# CPU.net
KiCad netlist of a schematic drawn in Altium Designer
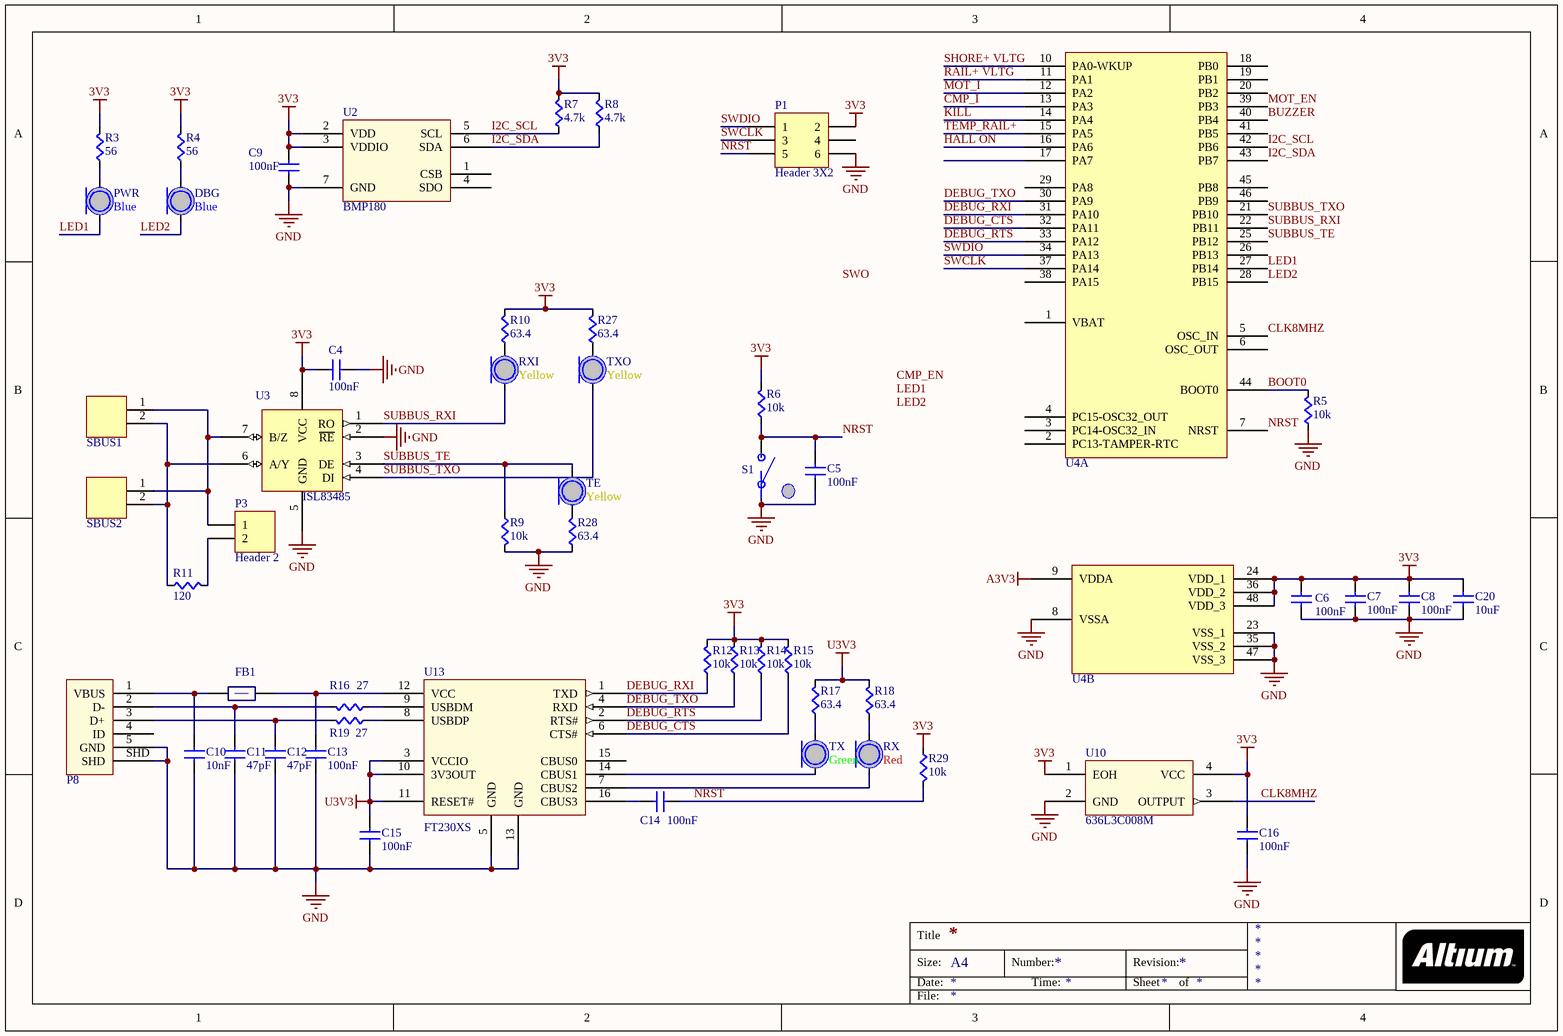
[diagram p0: CPU.SchDoc]

(export (version "E")
  (design (tool "Eeschema 10.0.6"))
  (components
    (comp (ref "C4")
      (value "100nF")
      (footprint "CAPC0603")
      (fields (field (name "Comment") "Cap"))
      (libsource (lib "SubjuGator8") (part "Cap"))
    )
    (comp (ref "C5")
      (value "100nF")
      (footprint "CAPC0603")
      (fields (field (name "Comment") "Cap"))
      (libsource (lib "SubjuGator8") (part "Cap"))
    )
    (comp (ref "C6")
      (value "100nF")
      (footprint "CAPC0603")
      (fields (field (name "Comment") "Cap"))
      (libsource (lib "SubjuGator8") (part "Cap"))
    )
    (comp (ref "C7")
      (value "100nF")
      (footprint "CAPC0603")
      (fields (field (name "Comment") "Cap"))
      (libsource (lib "SubjuGator8") (part "Cap"))
    )
    (comp (ref "C8")
      (value "100nF")
      (footprint "CAPC0603")
      (fields (field (name "Comment") "Cap"))
      (libsource (lib "SubjuGator8") (part "Cap"))
    )
    (comp (ref "C9")
      (value "100nF")
      (footprint "CAPC0603")
      (fields (field (name "Comment") "Cap"))
      (libsource (lib "SubjuGator8") (part "Cap"))
    )
    (comp (ref "C10")
      (value "10nF")
      (footprint "CAPC0603")
      (fields (field (name "Comment") "Cap"))
      (libsource (lib "SubjuGator8") (part "Cap"))
    )
    (comp (ref "C11")
      (value "47pF")
      (footprint "CAPC0603")
      (fields (field (name "Comment") "Cap"))
      (libsource (lib "SubjuGator8") (part "Cap"))
    )
    (comp (ref "C12")
      (value "47pF")
      (footprint "CAPC0603")
      (fields (field (name "Comment") "Cap"))
      (libsource (lib "SubjuGator8") (part "Cap"))
    )
    (comp (ref "C13")
      (value "100nF")
      (footprint "CAPC0603")
      (fields (field (name "Comment") "Cap"))
      (libsource (lib "SubjuGator8") (part "Cap"))
    )
    (comp (ref "C14")
      (value "100nF")
      (footprint "CAPC0603")
      (fields (field (name "Comment") "Cap"))
      (libsource (lib "SubjuGator8") (part "Cap"))
    )
    (comp (ref "C15")
      (value "100nF")
      (footprint "CAPC0603")
      (fields (field (name "Comment") "Cap"))
      (libsource (lib "SubjuGator8") (part "Cap"))
    )
    (comp (ref "C16")
      (value "100nF")
      (footprint "CAPC0603")
      (fields (field (name "Comment") "Cap"))
      (libsource (lib "SubjuGator8") (part "Cap"))
    )
    (comp (ref "C20")
      (value "10uF")
      (footprint "CAPC1206")
      (fields (field (name "Comment") "Cap"))
      (libsource (lib "SubjuGator8") (part "Cap"))
    )
    (comp (ref "DBG")
      (value "LED")
      (footprint "LED0805")
      (fields (field (name "COLOR") "Blue"))
      (libsource (lib "SubjuGator8") (part "LED"))
    )
    (comp (ref "FB1")
      (value "FBead")
      (footprint "RES0603")
      (description "Ferrite Bead")
      (libsource (lib "SubjuGator8") (part "FBead"))
    )
    (comp (ref "P1")
      (value "Header 3X2")
      (footprint "HDR2X3")
      (description "Header, 3-Pin, Dual row")
      (fields (field (name "PUBLISHER") "Altium Limited"))
      (libsource (lib "Miscellaneous Connectors") (part "Header 3X2"))
    )
    (comp (ref "P3")
      (value "Header 2")
      (footprint "HDR1X2")
      (description "Header, 2-Pin")
      (fields (field (name "PUBLISHER") "Altium Limited"))
      (libsource (lib "Miscellaneous Connectors") (part "Header 2"))
    )
    (comp (ref "P8")
      (value "UX60SC-MB-5ST")
      (footprint "UX60SC-MB-5ST")
      (description "USB Mini B Metal Shield SMT")
      (libsource (lib "SubjuGator8") (part "UX60SC-MB-5ST"))
    )
    (comp (ref "PWR")
      (value "LED")
      (footprint "LED0805")
      (fields (field (name "COLOR") "Blue"))
      (libsource (lib "SubjuGator8") (part "LED"))
    )
    (comp (ref "R3")
      (value "56")
      (footprint "RES0603")
      (fields (field (name "Comment") "Res"))
      (libsource (lib "SubjuGator8") (part "Res"))
    )
    (comp (ref "R4")
      (value "56")
      (footprint "RES0603")
      (fields (field (name "Comment") "Res"))
      (libsource (lib "SubjuGator8") (part "Res"))
    )
    (comp (ref "R5")
      (value "10k")
      (footprint "RES0603")
      (fields (field (name "Comment") "Res"))
      (libsource (lib "SubjuGator8") (part "Res"))
    )
    (comp (ref "R6")
      (value "10k")
      (footprint "RES0603")
      (fields (field (name "Comment") "Res"))
      (libsource (lib "SubjuGator8") (part "Res"))
    )
    (comp (ref "R7")
      (value "4.7k")
      (footprint "RES0603")
      (fields (field (name "Comment") "Res"))
      (libsource (lib "SubjuGator8") (part "Res"))
    )
    (comp (ref "R8")
      (value "4.7k")
      (footprint "RES0603")
      (fields (field (name "Comment") "Res"))
      (libsource (lib "SubjuGator8") (part "Res"))
    )
    (comp (ref "R9")
      (value "10k")
      (footprint "RES0603")
      (fields (field (name "Comment") "Res"))
      (libsource (lib "SubjuGator8") (part "Res"))
    )
    (comp (ref "R10")
      (value "63.4")
      (footprint "RES0603")
      (fields (field (name "Comment") "Res"))
      (libsource (lib "SubjuGator8") (part "Res"))
    )
    (comp (ref "R11")
      (value "120")
      (footprint "RES0603")
      (fields (field (name "Comment") "Res"))
      (libsource (lib "SubjuGator8") (part "Res"))
    )
    (comp (ref "R12")
      (value "10k")
      (footprint "RES0603")
      (fields (field (name "Comment") "Res"))
      (libsource (lib "SubjuGator8") (part "Res"))
    )
    (comp (ref "R13")
      (value "10k")
      (footprint "RES0603")
      (fields (field (name "Comment") "Res"))
      (libsource (lib "SubjuGator8") (part "Res"))
    )
    (comp (ref "R14")
      (value "10k")
      (footprint "RES0603")
      (fields (field (name "Comment") "Res"))
      (libsource (lib "SubjuGator8") (part "Res"))
    )
    (comp (ref "R15")
      (value "10k")
      (footprint "RES0603")
      (fields (field (name "Comment") "Res"))
      (libsource (lib "SubjuGator8") (part "Res"))
    )
    (comp (ref "R16")
      (value "27")
      (footprint "RES0603")
      (fields (field (name "Comment") "Res"))
      (libsource (lib "SubjuGator8") (part "Res"))
    )
    (comp (ref "R17")
      (value "63.4")
      (footprint "RES0603")
      (fields (field (name "Comment") "Res"))
      (libsource (lib "SubjuGator8") (part "Res"))
    )
    (comp (ref "R18")
      (value "63.4")
      (footprint "RES0603")
      (fields (field (name "Comment") "Res"))
      (libsource (lib "SubjuGator8") (part "Res"))
    )
    (comp (ref "R19")
      (value "27")
      (footprint "RES0603")
      (fields (field (name "Comment") "Res"))
      (libsource (lib "SubjuGator8") (part "Res"))
    )
    (comp (ref "R27")
      (value "63.4")
      (footprint "RES0603")
      (fields (field (name "Comment") "Res"))
      (libsource (lib "SubjuGator8") (part "Res"))
    )
    (comp (ref "R28")
      (value "63.4")
      (footprint "RES0603")
      (fields (field (name "Comment") "Res"))
      (libsource (lib "SubjuGator8") (part "Res"))
    )
    (comp (ref "R29")
      (value "10k")
      (footprint "RES0603")
      (fields (field (name "Comment") "Res"))
      (libsource (lib "SubjuGator8") (part "Res"))
    )
    (comp (ref "RX")
      (value "LED")
      (footprint "LED0805")
      (fields (field (name "COLOR") "Red"))
      (libsource (lib "SubjuGator8") (part "LED"))
    )
    (comp (ref "RXI")
      (value "LED")
      (footprint "LED0805")
      (fields (field (name "COLOR") "Yellow"))
      (libsource (lib "SubjuGator8") (part "LED"))
    )
    (comp (ref "S1")
      (value "Button")
      (footprint "PTS645xxxxSMTR92")
      (description "SPST Button")
      (libsource (lib "SubjuGator8") (part "Button"))
    )
    (comp (ref "SBUS1")
      (value "2-pin Horz Sherlock")
      (footprint "MOLEX-HDR-1X2-SHERLOCK-HORZ")
      (fields
        (field (name "MANUFACTURER PART NUMBER") "0353630260")
        (field (name "MANUFACTURER") "Molex Inc")
      )
      (libsource (lib "SubjuGator8") (part "MOLEX-HDR-1x2-SHERLOCK_RA"))
    )
    (comp (ref "SBUS2")
      (value "2-pin Horz Sherlock")
      (footprint "MOLEX-HDR-1X2-SHERLOCK-HORZ")
      (fields
        (field (name "MANUFACTURER PART NUMBER") "0353630260")
        (field (name "MANUFACTURER") "Molex Inc")
      )
      (libsource (lib "SubjuGator8") (part "MOLEX-HDR-1x2-SHERLOCK_RA"))
    )
    (comp (ref "TE")
      (value "LED")
      (footprint "LED0805")
      (fields (field (name "COLOR") "Yellow"))
      (libsource (lib "SubjuGator8") (part "LED"))
    )
    (comp (ref "TX")
      (value "LED")
      (footprint "LED0805")
      (fields (field (name "COLOR") "Green"))
      (libsource (lib "SubjuGator8") (part "LED"))
    )
    (comp (ref "TXO")
      (value "LED")
      (footprint "LED0805")
      (fields (field (name "COLOR") "Yellow"))
      (libsource (lib "SubjuGator8") (part "LED"))
    )
    (comp (ref "U2")
      (value "BMP180")
      (footprint "BMP180")
      (description "Digital Pressure Sensor")
      (libsource (lib "SubjuGator8") (part "BMP180"))
    )
    (comp (ref "U3")
      (value "ISL83485")
      (footprint "ISL8348xIBZ")
      (description "3.3V RS485 Transceiver")
      (libsource (lib "SubjuGator8") (part "ISL83485"))
    )
    (comp (ref "U4")
      (value "STM32F103C8T7")
      (footprint "STM32F103C8T7")
      (description "MCU ARM 32BIT 64K FLASH 48-LQFP")
      (libsource (lib "SubjuGator8") (part "STM32F103C8T7"))
    )
    (comp (ref "U10")
      (value "636L3C008M")
      (footprint "636L3C")
      (description "HCMOS/TTL Clock Oscillator")
      (libsource (lib "SubjuGator8") (part "636L3C"))
    )
    (comp (ref "U13")
      (value "FT230XS")
      (footprint "FT230XS")
      (description "USB To Basic UART IC")
      (libsource (lib "SubjuGator8") (part "FT230XS"))
    )
  )
  (nets
    (net (code "1") (name "/BOOT0") (class "Default")
      (node (ref "R5") (pin "1") (pinfunction "A_1") (pintype "passive"))
      (node (ref "U4") (pin "44") (pinfunction "BOOT0_44") (pintype "passive"))
    )
    (net (code "2") (name "/BUZZER") (class "Default")
      (node (ref "U4") (pin "40") (pinfunction "PB4_40") (pintype "passive"))
    )
    (net (code "3") (name "/CLK8MHZ") (class "Default")
      (node (ref "U10") (pin "3") (pinfunction "OUTPUT_3") (pintype "output"))
      (node (ref "U4") (pin "5") (pinfunction "OSC_IN_5") (pintype "passive"))
    )
    (net (code "5") (name "/CMP_I") (class "Default")
      (node (ref "U4") (pin "13") (pinfunction "PA3_13") (pintype "passive"))
    )
    (net (code "6") (name "/DEBUG_CTS") (class "Default")
      (node (ref "R15") (pin "2") (pinfunction "B_2") (pintype "passive"))
      (node (ref "U13") (pin "6") (pinfunction "CTS#_6") (pintype "input"))
      (node (ref "U4") (pin "32") (pinfunction "PA11_32") (pintype "passive"))
    )
    (net (code "7") (name "/DEBUG_RTS") (class "Default")
      (node (ref "R14") (pin "2") (pinfunction "B_2") (pintype "passive"))
      (node (ref "U13") (pin "2") (pinfunction "RTS#_2") (pintype "output"))
      (node (ref "U4") (pin "33") (pinfunction "PA12_33") (pintype "passive"))
    )
    (net (code "8") (name "/DEBUG_RXI") (class "Default")
      (node (ref "R12") (pin "2") (pinfunction "B_2") (pintype "passive"))
      (node (ref "U13") (pin "1") (pinfunction "TXD_1") (pintype "output"))
      (node (ref "U4") (pin "31") (pinfunction "PA10_31") (pintype "passive"))
    )
    (net (code "9") (name "/DEBUG_TXO") (class "Default")
      (node (ref "R13") (pin "2") (pinfunction "B_2") (pintype "passive"))
      (node (ref "U13") (pin "4") (pinfunction "RXD_4") (pintype "input"))
      (node (ref "U4") (pin "30") (pinfunction "PA9_30") (pintype "passive"))
    )
    (net (code "10") (name "/HALL ON") (class "Default")
      (node (ref "U4") (pin "16") (pinfunction "PA6_16") (pintype "passive"))
    )
    (net (code "11") (name "/I2C_SCL") (class "Default")
      (node (ref "R7") (pin "2") (pinfunction "B_2") (pintype "passive"))
      (node (ref "U2") (pin "5") (pinfunction "SCL_5") (pintype "passive"))
      (node (ref "U4") (pin "42") (pinfunction "PB6_42") (pintype "passive"))
    )
    (net (code "12") (name "/I2C_SDA") (class "Default")
      (node (ref "R8") (pin "2") (pinfunction "B_2") (pintype "passive"))
      (node (ref "U2") (pin "6") (pinfunction "SDA_6") (pintype "passive"))
      (node (ref "U4") (pin "43") (pinfunction "PB7_43") (pintype "passive"))
    )
    (net (code "13") (name "/KILL") (class "Default")
      (node (ref "U4") (pin "14") (pinfunction "PA4_14") (pintype "passive"))
    )
    (net (code "14") (name "/LED1") (class "Default")
      (node (ref "PWR") (pin "C") (pinfunction "C_C") (pintype "passive"))
      (node (ref "U4") (pin "27") (pinfunction "PB14_27") (pintype "passive"))
    )
    (net (code "15") (name "/LED2") (class "Default")
      (node (ref "DBG") (pin "C") (pinfunction "C_C") (pintype "passive"))
      (node (ref "U4") (pin "28") (pinfunction "PB15_28") (pintype "passive"))
    )
    (net (code "16") (name "/MOT_EN") (class "Default")
      (node (ref "U4") (pin "39") (pinfunction "PB3_39") (pintype "passive"))
    )
    (net (code "17") (name "/MOT_I") (class "Default")
      (node (ref "U4") (pin "12") (pinfunction "PA2_12") (pintype "passive"))
    )
    (net (code "18") (name "/NRST") (class "Default")
      (node (ref "C14") (pin "2") (pinfunction "B_2") (pintype "passive"))
      (node (ref "C5") (pin "1") (pinfunction "A_1") (pintype "passive"))
      (node (ref "P1") (pin "5") (pinfunction "5_5") (pintype "passive"))
      (node (ref "R29") (pin "2") (pinfunction "B_2") (pintype "passive"))
      (node (ref "R6") (pin "2") (pinfunction "B_2") (pintype "passive"))
      (node (ref "S1") (pin "B") (pinfunction "B_B") (pintype "passive"))
      (node (ref "U4") (pin "7") (pinfunction "NRST_7") (pintype "passive"))
    )
    (net (code "19") (name "/RAIL+ VLTG") (class "Default")
      (node (ref "U4") (pin "11") (pinfunction "PA1_11") (pintype "passive"))
    )
    (net (code "20") (name "/SHORE+ VLTG") (class "Default")
      (node (ref "U4") (pin "10") (pinfunction "PA0-WKUP_10") (pintype "passive"))
    )
    (net (code "21") (name "/SUBBUS_RXI") (class "Default")
      (node (ref "RXI") (pin "C") (pinfunction "C_C") (pintype "passive"))
      (node (ref "U3") (pin "1") (pinfunction "RO_1") (pintype "output"))
      (node (ref "U4") (pin "22") (pinfunction "PB11_22") (pintype "passive"))
    )
    (net (code "22") (name "/SUBBUS_TE") (class "Default")
      (node (ref "R9") (pin "1") (pinfunction "A_1") (pintype "passive"))
      (node (ref "TE") (pin "A") (pinfunction "A_A") (pintype "passive"))
      (node (ref "U3") (pin "3") (pinfunction "DE_3") (pintype "input"))
      (node (ref "U4") (pin "25") (pinfunction "PB12_25") (pintype "passive"))
    )
    (net (code "23") (name "/SUBBUS_TXO") (class "Default")
      (node (ref "TXO") (pin "C") (pinfunction "C_C") (pintype "passive"))
      (node (ref "U3") (pin "4") (pinfunction "DI_4") (pintype "input"))
      (node (ref "U4") (pin "21") (pinfunction "PB10_21") (pintype "passive"))
    )
    (net (code "24") (name "/SWCLK") (class "Default")
      (node (ref "P1") (pin "3") (pinfunction "3_3") (pintype "passive"))
      (node (ref "U4") (pin "37") (pinfunction "PA14_37") (pintype "passive"))
    )
    (net (code "25") (name "/SWDIO") (class "Default")
      (node (ref "P1") (pin "1") (pinfunction "1_1") (pintype "passive"))
      (node (ref "U4") (pin "34") (pinfunction "PA13_34") (pintype "passive"))
    )
    (net (code "27") (name "/TEMP_RAIL+") (class "Default")
      (node (ref "U4") (pin "15") (pinfunction "PA5_15") (pintype "passive"))
    )
    (net (code "28") (name "3V3") (class "Default")
      (node (ref "C16") (pin "1") (pinfunction "A_1") (pintype "passive"))
      (node (ref "C20") (pin "2") (pinfunction "B_2") (pintype "passive"))
      (node (ref "C4") (pin "2") (pinfunction "B_2") (pintype "passive"))
      (node (ref "C6") (pin "1") (pinfunction "A_1") (pintype "passive"))
      (node (ref "C7") (pin "1") (pinfunction "A_1") (pintype "passive"))
      (node (ref "C8") (pin "1") (pinfunction "A_1") (pintype "passive"))
      (node (ref "C9") (pin "1") (pinfunction "A_1") (pintype "passive"))
      (node (ref "P1") (pin "2") (pinfunction "2_2") (pintype "passive"))
      (node (ref "R10") (pin "1") (pinfunction "A_1") (pintype "passive"))
      (node (ref "R12") (pin "1") (pinfunction "A_1") (pintype "passive"))
      (node (ref "R13") (pin "1") (pinfunction "A_1") (pintype "passive"))
      (node (ref "R14") (pin "1") (pinfunction "A_1") (pintype "passive"))
      (node (ref "R15") (pin "1") (pinfunction "A_1") (pintype "passive"))
      (node (ref "R27") (pin "1") (pinfunction "A_1") (pintype "passive"))
      (node (ref "R29") (pin "1") (pinfunction "A_1") (pintype "passive"))
      (node (ref "R3") (pin "1") (pinfunction "A_1") (pintype "passive"))
      (node (ref "R4") (pin "1") (pinfunction "A_1") (pintype "passive"))
      (node (ref "R6") (pin "1") (pinfunction "A_1") (pintype "passive"))
      (node (ref "R7") (pin "1") (pinfunction "A_1") (pintype "passive"))
      (node (ref "R8") (pin "1") (pinfunction "A_1") (pintype "passive"))
      (node (ref "U10") (pin "1") (pinfunction "EOH_1") (pintype "passive"))
      (node (ref "U10") (pin "4") (pinfunction "VCC_4") (pintype "power_in"))
      (node (ref "U2") (pin "2") (pinfunction "VDD_2") (pintype "power_in"))
      (node (ref "U2") (pin "3") (pinfunction "VDDIO_3") (pintype "power_in"))
      (node (ref "U3") (pin "8") (pinfunction "VCC_8") (pintype "power_in"))
      (node (ref "U4") (pin "24") (pinfunction "VDD_1_24") (pintype "passive"))
      (node (ref "U4") (pin "36") (pinfunction "VDD_2_36") (pintype "passive"))
      (node (ref "U4") (pin "48") (pinfunction "VDD_3_48") (pintype "passive"))
    )
    (net (code "29") (name "A3V3") (class "Default")
      (node (ref "U4") (pin "9") (pinfunction "VDDA_9") (pintype "passive"))
    )
    (net (code "30") (name "GND") (class "Default")
      (node (ref "C10") (pin "2") (pinfunction "B_2") (pintype "passive"))
      (node (ref "C11") (pin "2") (pinfunction "B_2") (pintype "passive"))
      (node (ref "C12") (pin "2") (pinfunction "B_2") (pintype "passive"))
      (node (ref "C13") (pin "2") (pinfunction "B_2") (pintype "passive"))
      (node (ref "C15") (pin "2") (pinfunction "B_2") (pintype "passive"))
      (node (ref "C16") (pin "2") (pinfunction "B_2") (pintype "passive"))
      (node (ref "C20") (pin "1") (pinfunction "A_1") (pintype "passive"))
      (node (ref "C4") (pin "1") (pinfunction "A_1") (pintype "passive"))
      (node (ref "C5") (pin "2") (pinfunction "B_2") (pintype "passive"))
      (node (ref "C6") (pin "2") (pinfunction "B_2") (pintype "passive"))
      (node (ref "C7") (pin "2") (pinfunction "B_2") (pintype "passive"))
      (node (ref "C8") (pin "2") (pinfunction "B_2") (pintype "passive"))
      (node (ref "C9") (pin "2") (pinfunction "B_2") (pintype "passive"))
      (node (ref "P1") (pin "6") (pinfunction "6_6") (pintype "passive"))
      (node (ref "P8") (pin "5") (pinfunction "GND_5") (pintype "passive"))
      (node (ref "P8") (pin "SHD") (pinfunction "SHD_SHD") (pintype "passive"))
      (node (ref "R28") (pin "2") (pinfunction "B_2") (pintype "passive"))
      (node (ref "R5") (pin "2") (pinfunction "B_2") (pintype "passive"))
      (node (ref "R9") (pin "2") (pinfunction "B_2") (pintype "passive"))
      (node (ref "S1") (pin "A") (pinfunction "A_A") (pintype "passive"))
      (node (ref "U10") (pin "2") (pinfunction "GND_2") (pintype "power_in"))
      (node (ref "U13") (pin "13") (pinfunction "GND_13") (pintype "power_in"))
      (node (ref "U13") (pin "5") (pinfunction "GND_5") (pintype "power_in"))
      (node (ref "U2") (pin "7") (pinfunction "GND_7") (pintype "power_in"))
      (node (ref "U3") (pin "2") (pinfunction "~{RE}_2") (pintype "input"))
      (node (ref "U3") (pin "5") (pinfunction "GND_5") (pintype "power_in"))
      (node (ref "U4") (pin "23") (pinfunction "VSS_1_23") (pintype "passive"))
      (node (ref "U4") (pin "35") (pinfunction "VSS_2_35") (pintype "passive"))
      (node (ref "U4") (pin "47") (pinfunction "VSS_3_47") (pintype "passive"))
      (node (ref "U4") (pin "8") (pinfunction "VSSA_8") (pintype "passive"))
    )
    (net (code "31") (name "Net-(C10-A)") (class "Default")
      (node (ref "C10") (pin "1") (pinfunction "A_1") (pintype "passive"))
      (node (ref "FB1") (pin "2") (pinfunction "B_2") (pintype "passive"))
      (node (ref "P8") (pin "1") (pinfunction "VBUS_1") (pintype "passive"))
    )
    (net (code "32") (name "Net-(C11-A)") (class "Default")
      (node (ref "C11") (pin "1") (pinfunction "A_1") (pintype "passive"))
      (node (ref "P8") (pin "2") (pinfunction "D-_2") (pintype "passive"))
      (node (ref "R16") (pin "1") (pinfunction "A_1") (pintype "passive"))
    )
    (net (code "33") (name "Net-(C12-A)") (class "Default")
      (node (ref "C12") (pin "1") (pinfunction "A_1") (pintype "passive"))
      (node (ref "P8") (pin "3") (pinfunction "D+_3") (pintype "passive"))
      (node (ref "R19") (pin "1") (pinfunction "A_1") (pintype "passive"))
    )
    (net (code "34") (name "Net-(C13-A)") (class "Default")
      (node (ref "C13") (pin "1") (pinfunction "A_1") (pintype "passive"))
      (node (ref "FB1") (pin "1") (pinfunction "A_1") (pintype "passive"))
      (node (ref "U13") (pin "12") (pinfunction "VCC_12") (pintype "power_in"))
    )
    (net (code "35") (name "Net-(C14-A)") (class "Default")
      (node (ref "C14") (pin "1") (pinfunction "A_1") (pintype "passive"))
      (node (ref "U13") (pin "16") (pinfunction "CBUS3_16") (pintype "passive"))
    )
    (net (code "36") (name "Net-(R3-B)") (class "Default")
      (node (ref "PWR") (pin "A") (pinfunction "A_A") (pintype "passive"))
      (node (ref "R3") (pin "2") (pinfunction "B_2") (pintype "passive"))
    )
    (net (code "37") (name "Net-(R4-B)") (class "Default")
      (node (ref "DBG") (pin "A") (pinfunction "A_A") (pintype "passive"))
      (node (ref "R4") (pin "2") (pinfunction "B_2") (pintype "passive"))
    )
    (net (code "38") (name "Net-(R10-B)") (class "Default")
      (node (ref "R10") (pin "2") (pinfunction "B_2") (pintype "passive"))
      (node (ref "RXI") (pin "A") (pinfunction "A_A") (pintype "passive"))
    )
    (net (code "39") (name "Net-(R11-A)") (class "Default")
      (node (ref "P3") (pin "2") (pinfunction "2_2") (pintype "passive"))
      (node (ref "R11") (pin "1") (pinfunction "A_1") (pintype "passive"))
    )
    (net (code "40") (name "Net-(R11-B)") (class "Default")
      (node (ref "R11") (pin "2") (pinfunction "B_2") (pintype "passive"))
      (node (ref "SBUS1") (pin "2") (pinfunction "2_2") (pintype "passive"))
      (node (ref "SBUS2") (pin "2") (pinfunction "2_2") (pintype "passive"))
      (node (ref "U3") (pin "6") (pinfunction "A/Y_6") (pintype "bidirectional"))
    )
    (net (code "41") (name "Net-(R16-B)") (class "Default")
      (node (ref "R16") (pin "2") (pinfunction "B_2") (pintype "passive"))
      (node (ref "U13") (pin "9") (pinfunction "USBDM_9") (pintype "passive"))
    )
    (net (code "42") (name "Net-(R17-B)") (class "Default")
      (node (ref "R17") (pin "2") (pinfunction "B_2") (pintype "passive"))
      (node (ref "TX") (pin "A") (pinfunction "A_A") (pintype "passive"))
    )
    (net (code "43") (name "Net-(R18-B)") (class "Default")
      (node (ref "R18") (pin "2") (pinfunction "B_2") (pintype "passive"))
      (node (ref "RX") (pin "A") (pinfunction "A_A") (pintype "passive"))
    )
    (net (code "44") (name "Net-(R19-B)") (class "Default")
      (node (ref "R19") (pin "2") (pinfunction "B_2") (pintype "passive"))
      (node (ref "U13") (pin "8") (pinfunction "USBDP_8") (pintype "passive"))
    )
    (net (code "45") (name "Net-(R27-B)") (class "Default")
      (node (ref "R27") (pin "2") (pinfunction "B_2") (pintype "passive"))
      (node (ref "TXO") (pin "A") (pinfunction "A_A") (pintype "passive"))
    )
    (net (code "46") (name "Net-(R28-A)") (class "Default")
      (node (ref "R28") (pin "1") (pinfunction "A_1") (pintype "passive"))
      (node (ref "TE") (pin "C") (pinfunction "C_C") (pintype "passive"))
    )
    (net (code "47") (name "Net-(U3-B{slash}Z)") (class "Default")
      (node (ref "P3") (pin "1") (pinfunction "1_1") (pintype "passive"))
      (node (ref "SBUS1") (pin "1") (pinfunction "1_1") (pintype "passive"))
      (node (ref "SBUS2") (pin "1") (pinfunction "1_1") (pintype "passive"))
      (node (ref "U3") (pin "7") (pinfunction "B/Z_7") (pintype "bidirectional"))
    )
    (net (code "48") (name "Net-(U13-CBUS1)") (class "Default")
      (node (ref "TX") (pin "C") (pinfunction "C_C") (pintype "passive"))
      (node (ref "U13") (pin "14") (pinfunction "CBUS1_14") (pintype "passive"))
    )
    (net (code "49") (name "Net-(U13-CBUS2)") (class "Default")
      (node (ref "RX") (pin "C") (pinfunction "C_C") (pintype "passive"))
      (node (ref "U13") (pin "7") (pinfunction "CBUS2_7") (pintype "passive"))
    )
    (net (code "50") (name "U3V3") (class "Default")
      (node (ref "C15") (pin "1") (pinfunction "A_1") (pintype "passive"))
      (node (ref "R17") (pin "1") (pinfunction "A_1") (pintype "passive"))
      (node (ref "R18") (pin "1") (pinfunction "A_1") (pintype "passive"))
      (node (ref "U13") (pin "10") (pinfunction "3V3OUT_10") (pintype "passive"))
      (node (ref "U13") (pin "11") (pinfunction "RESET#_11") (pintype "passive"))
      (node (ref "U13") (pin "3") (pinfunction "VCCIO_3") (pintype "power_in"))
    )
    (net (code "51") (name "unconnected-(P1-Pad4)") (class "Default")
      (node (ref "P1") (pin "4") (pinfunction "4_4") (pintype "passive"))
    )
    (net (code "52") (name "unconnected-(P8-ID-Pad4)") (class "Default")
      (node (ref "P8") (pin "4") (pinfunction "ID_4") (pintype "passive"))
    )
    (net (code "53") (name "unconnected-(U2-CSB-Pad1)") (class "Default")
      (node (ref "U2") (pin "1") (pinfunction "CSB_1") (pintype "passive"))
    )
    (net (code "54") (name "unconnected-(U2-SDO-Pad4)") (class "Default")
      (node (ref "U2") (pin "4") (pinfunction "SDO_4") (pintype "passive"))
    )
    (net (code "55") (name "unconnected-(U4A-OSC_OUT-Pad6)") (class "Default")
      (node (ref "U4") (pin "6") (pinfunction "OSC_OUT_6") (pintype "passive"))
    )
    (net (code "56") (name "unconnected-(U4A-PA7-Pad17)") (class "Default")
      (node (ref "U4") (pin "17") (pinfunction "PA7_17") (pintype "passive"))
    )
    (net (code "57") (name "unconnected-(U4A-PA8-Pad29)") (class "Default")
      (node (ref "U4") (pin "29") (pinfunction "PA8_29") (pintype "passive"))
    )
    (net (code "58") (name "unconnected-(U4A-PA15-Pad38)") (class "Default")
      (node (ref "U4") (pin "38") (pinfunction "PA15_38") (pintype "passive"))
    )
    (net (code "59") (name "unconnected-(U4A-PB0-Pad18)") (class "Default")
      (node (ref "U4") (pin "18") (pinfunction "PB0_18") (pintype "passive"))
    )
    (net (code "60") (name "unconnected-(U4A-PB1-Pad19)") (class "Default")
      (node (ref "U4") (pin "19") (pinfunction "PB1_19") (pintype "passive"))
    )
    (net (code "61") (name "unconnected-(U4A-PB2-Pad20)") (class "Default")
      (node (ref "U4") (pin "20") (pinfunction "PB2_20") (pintype "passive"))
    )
    (net (code "62") (name "unconnected-(U4A-PB5-Pad41)") (class "Default")
      (node (ref "U4") (pin "41") (pinfunction "PB5_41") (pintype "passive"))
    )
    (net (code "63") (name "unconnected-(U4A-PB8-Pad45)") (class "Default")
      (node (ref "U4") (pin "45") (pinfunction "PB8_45") (pintype "passive"))
    )
    (net (code "64") (name "unconnected-(U4A-PB9-Pad46)") (class "Default")
      (node (ref "U4") (pin "46") (pinfunction "PB9_46") (pintype "passive"))
    )
    (net (code "65") (name "unconnected-(U4A-PB13-Pad26)") (class "Default")
      (node (ref "U4") (pin "26") (pinfunction "PB13_26") (pintype "passive"))
    )
    (net (code "66") (name "unconnected-(U4A-PC13-TAMPER-RTC-Pad2)") (class "Default")
      (node (ref "U4") (pin "2") (pinfunction "PC13-TAMPER-RTC_2") (pintype "passive"))
    )
    (net (code "67") (name "unconnected-(U4A-PC14-OSC32_IN-Pad3)") (class "Default")
      (node (ref "U4") (pin "3") (pinfunction "PC14-OSC32_IN_3") (pintype "passive"))
    )
    (net (code "68") (name "unconnected-(U4A-PC15-OSC32_OUT-Pad4)") (class "Default")
      (node (ref "U4") (pin "4") (pinfunction "PC15-OSC32_OUT_4") (pintype "passive"))
    )
    (net (code "69") (name "unconnected-(U4A-VBAT-Pad1)") (class "Default")
      (node (ref "U4") (pin "1") (pinfunction "VBAT_1") (pintype "passive"))
    )
    (net (code "70") (name "unconnected-(U13-CBUS0-Pad15)") (class "Default")
      (node (ref "U13") (pin "15") (pinfunction "CBUS0_15") (pintype "passive"))
    )
  )
)
